# nevma.net
KiCad netlist of a schematic drawn in EAGLE
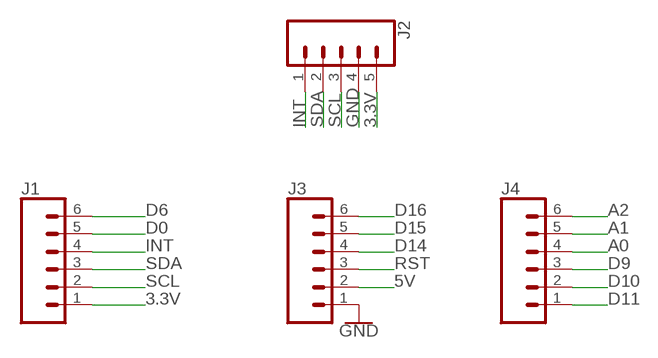
[diagram p0: schematic, sheet 1]

(export (version "E")
  (design (tool "Eeschema 10.0.6"))
  (components
    (comp (ref "J1")
      (value "CONN_06LOCK")
      (footprint "eagle-import:1X06_LOCK")
      (libsource (lib "eagle-import") (part "CONN_06LOCK"))
    )
    (comp (ref "J2")
      (value "CONN_05LOCK")
      (footprint "eagle-import:1X05_LOCK")
      (libsource (lib "eagle-import") (part "CONN_05LOCK"))
    )
    (comp (ref "J3")
      (value "CONN_06LOCK")
      (footprint "eagle-import:1X06_LOCK")
      (libsource (lib "eagle-import") (part "CONN_06LOCK"))
    )
    (comp (ref "J4")
      (value "CONN_06LOCK")
      (footprint "eagle-import:1X06_LOCK")
      (libsource (lib "eagle-import") (part "CONN_06LOCK"))
    )
  )
  (nets
    (net (code "1") (name "/3.3V") (class "Default")
      (node (ref "J1") (pin "1") (pinfunction "1_1") (pintype "passive"))
      (node (ref "J2") (pin "5") (pinfunction "5_5") (pintype "passive"))
    )
    (net (code "2") (name "/5V") (class "Default")
      (node (ref "J3") (pin "2") (pinfunction "2_2") (pintype "passive"))
    )
    (net (code "3") (name "/A0") (class "Default")
      (node (ref "J4") (pin "4") (pinfunction "4_4") (pintype "passive"))
    )
    (net (code "4") (name "/A1") (class "Default")
      (node (ref "J4") (pin "5") (pinfunction "5_5") (pintype "passive"))
    )
    (net (code "5") (name "/A2") (class "Default")
      (node (ref "J4") (pin "6") (pinfunction "6_6") (pintype "passive"))
    )
    (net (code "6") (name "/D0") (class "Default")
      (node (ref "J1") (pin "5") (pinfunction "5_5") (pintype "passive"))
    )
    (net (code "7") (name "/D6") (class "Default")
      (node (ref "J1") (pin "6") (pinfunction "6_6") (pintype "passive"))
    )
    (net (code "8") (name "/D9") (class "Default")
      (node (ref "J4") (pin "3") (pinfunction "3_3") (pintype "passive"))
    )
    (net (code "9") (name "/D10") (class "Default")
      (node (ref "J4") (pin "2") (pinfunction "2_2") (pintype "passive"))
    )
    (net (code "10") (name "/D11") (class "Default")
      (node (ref "J4") (pin "1") (pinfunction "1_1") (pintype "passive"))
    )
    (net (code "11") (name "/D14") (class "Default")
      (node (ref "J3") (pin "4") (pinfunction "4_4") (pintype "passive"))
    )
    (net (code "12") (name "/D15") (class "Default")
      (node (ref "J3") (pin "5") (pinfunction "5_5") (pintype "passive"))
    )
    (net (code "13") (name "/D16") (class "Default")
      (node (ref "J3") (pin "6") (pinfunction "6_6") (pintype "passive"))
    )
    (net (code "14") (name "/INT") (class "Default")
      (node (ref "J1") (pin "4") (pinfunction "4_4") (pintype "passive"))
      (node (ref "J2") (pin "1") (pinfunction "1_1") (pintype "passive"))
    )
    (net (code "15") (name "/RST") (class "Default")
      (node (ref "J3") (pin "3") (pinfunction "3_3") (pintype "passive"))
    )
    (net (code "16") (name "/SCL") (class "Default")
      (node (ref "J1") (pin "2") (pinfunction "2_2") (pintype "passive"))
      (node (ref "J2") (pin "3") (pinfunction "3_3") (pintype "passive"))
    )
    (net (code "17") (name "/SDA") (class "Default")
      (node (ref "J1") (pin "3") (pinfunction "3_3") (pintype "passive"))
      (node (ref "J2") (pin "2") (pinfunction "2_2") (pintype "passive"))
    )
    (net (code "18") (name "GND") (class "Default")
      (node (ref "J2") (pin "4") (pinfunction "4_4") (pintype "passive"))
      (node (ref "J3") (pin "1") (pinfunction "1_1") (pintype "passive"))
    )
  )
)
